# Triangular_Wave.net
KiCad netlist of a schematic drawn in Altium Designer
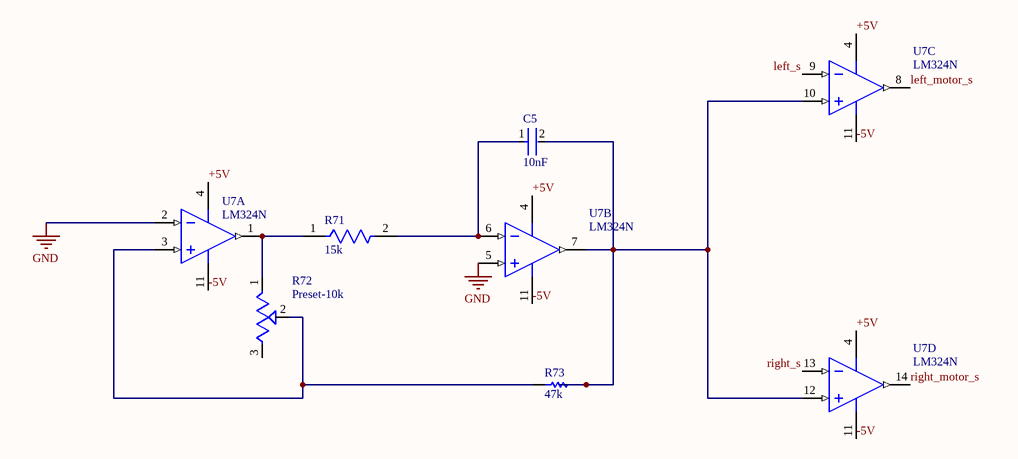
[diagram p0: Triangular_Wave.SchDoc]

(export (version "E")
  (design (tool "Eeschema 10.0.6"))
  (components
    (comp (ref "C5")
      (value "10nF")
      (footprint "FP-C0805C-DN-MFG")
      (description "CAP CER 10000PF 50V X7R 0805; C0805C103K5RACTU")
      (fields (field (name "MANUFACTURER PART NUMBER") "C0805C103K5RACTU") (field (name "TOLERANCE") "0.1"))
      (libsource (lib "Capacitors") (part "10nF"))
    )
    (comp (ref "R71")
      (value "15k")
      (footprint "FP-CRCW0805-e3-IPC_C")
      (description "RES Thick Film, 15kΩ, 1%, 0.125W, 100ppm/°C, 0805; CRCW080515K0FKEA")
      (fields (field (name "TOLERANCE") "1%"))
      (libsource (lib "Resistors") (part "15k"))
    )
    (comp (ref "R72")
      (value "Preset-10k")
      (footprint "TRIM_3306F-1-103")
      (description "TRIMMER - 6MM ROUND, SINGLE-TURN,CERMET, 10K OHMS ¦ Bourns 3306F-1-103")
      (fields (field (name "MF") "Bourns") (field (name "MP") "3306F-1-103"))
      (libsource (lib "3306F-1-103") (part "Preset"))
    )
    (comp (ref "R73")
      (value "47k")
      (footprint "RESC2013X60X35NL10T20")
      (fields (field (name "MANUFACTURER") "Yageo"))
      (libsource (lib "Resistors") (part "47k"))
    )
    (comp (ref "U7")
      (value "LM324N")
      (footprint "N0014A")
      (description "Low Power Quad Operational Amplifier, 14-pin MDIP")
      (fields (field (name "MANUFACTURER") "Texas Instruments"))
      (libsource (lib "ICs") (part "LM324N"))
    )
  )
  (nets
    (net (code "1") (name "/+5V") (class "Default")
      (node (ref "U7") (pin "4") (pinfunction "V+_4") (pintype "power_in"))
    )
    (net (code "2") (name "/-5V") (class "Default")
      (node (ref "U7") (pin "11") (pinfunction "GND_11") (pintype "power_in"))
    )
    (net (code "3") (name "/left_motor_s") (class "Default")
      (node (ref "U7") (pin "8") (pinfunction "OUT3_8") (pintype "output"))
    )
    (net (code "4") (name "/left_s") (class "Default")
      (node (ref "U7") (pin "9") (pinfunction "IN3-_9") (pintype "input"))
    )
    (net (code "5") (name "/right_motor_s") (class "Default")
      (node (ref "U7") (pin "14") (pinfunction "OUT4_14") (pintype "output"))
    )
    (net (code "6") (name "/right_s") (class "Default")
      (node (ref "U7") (pin "13") (pinfunction "IN4-_13") (pintype "input"))
    )
    (net (code "7") (name "GND") (class "Default")
      (node (ref "U7") (pin "2") (pinfunction "IN1-_2") (pintype "input"))
      (node (ref "U7") (pin "5") (pinfunction "IN2+_5") (pintype "input"))
    )
    (net (code "8") (name "Net-(R72-CCW)") (class "Default")
      (node (ref "R71") (pin "1") (pinfunction "1_1") (pintype "passive"))
      (node (ref "R72") (pin "1") (pinfunction "CCW_1") (pintype "passive"))
      (node (ref "U7") (pin "1") (pinfunction "OUT1_1") (pintype "output"))
    )
    (net (code "9") (name "Net-(R72-W)") (class "Default")
      (node (ref "R72") (pin "2") (pinfunction "W_2") (pintype "passive"))
      (node (ref "R73") (pin "1") (pinfunction "1_1") (pintype "passive"))
      (node (ref "U7") (pin "3") (pinfunction "IN1+_3") (pintype "input"))
    )
    (net (code "10") (name "Net-(U7B-IN2-)") (class "Default")
      (node (ref "C5") (pin "1") (pinfunction "1_1") (pintype "passive"))
      (node (ref "R71") (pin "2") (pinfunction "2_2") (pintype "passive"))
      (node (ref "U7") (pin "6") (pinfunction "IN2-_6") (pintype "input"))
    )
    (net (code "11") (name "Net-(U7B-OUT2)") (class "Default")
      (node (ref "C5") (pin "2") (pinfunction "2_2") (pintype "passive"))
      (node (ref "R73") (pin "2") (pinfunction "2_2") (pintype "passive"))
      (node (ref "U7") (pin "10") (pinfunction "IN3+_10") (pintype "input"))
      (node (ref "U7") (pin "12") (pinfunction "IN4+_12") (pintype "input"))
      (node (ref "U7") (pin "7") (pinfunction "OUT2_7") (pintype "output"))
    )
    (net (code "12") (name "unconnected-(R72-CW-Pad3)") (class "Default")
      (node (ref "R72") (pin "3") (pinfunction "CW_3") (pintype "passive"))
    )
  )
)
